# V_1.net
KiCad netlist of a schematic drawn in Altium Designer
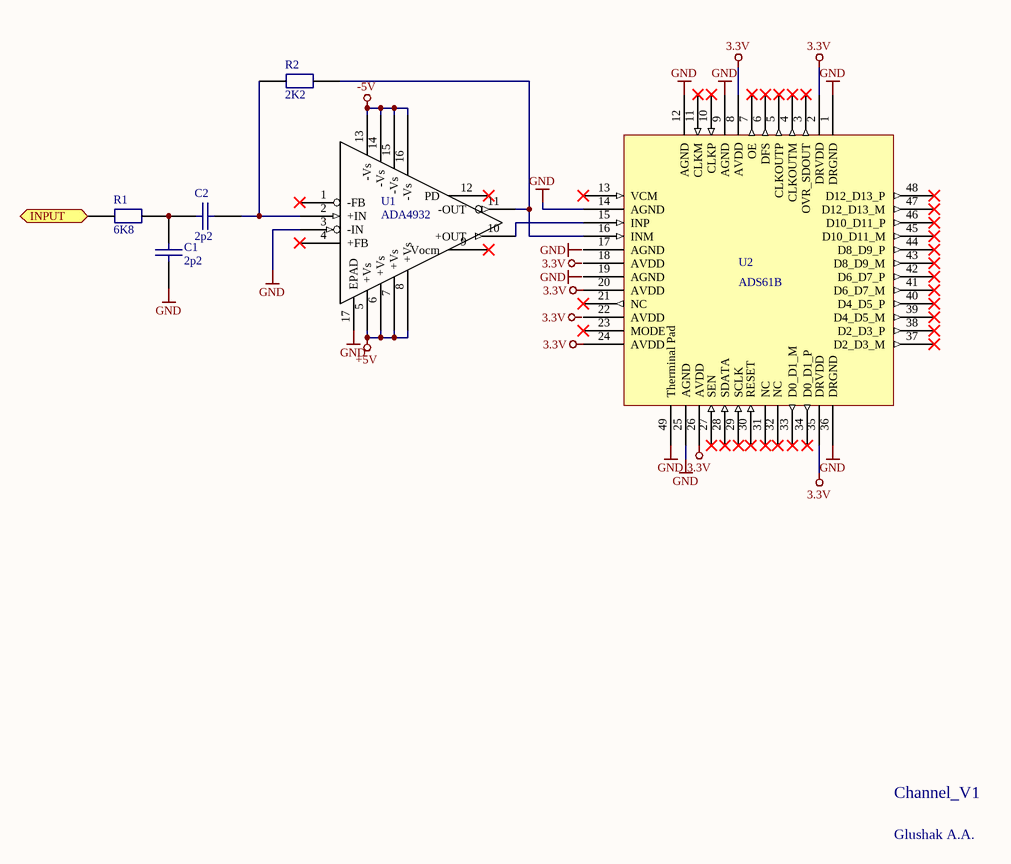
[diagram p0: V_1.SchDoc]

(export (version "E")
  (design (tool "Eeschema 10.0.6"))
  (components
    (comp (ref "C1") (value "2p2") (footprint "Cap0805") (libsource (lib "V_1") (part "Cap")))
    (comp (ref "C2") (value "2p2") (footprint "Cap0805") (libsource (lib "V_1") (part "Cap")))
    (comp (ref "R1") (value "6K8") (footprint "Res0805") (libsource (lib "V_1") (part "Res")))
    (comp (ref "R2") (value "2K2") (footprint "Res0805") (libsource (lib "V_1") (part "Res")))
    (comp (ref "U1") (value "ADA4932") (footprint "ADA4932") (libsource (lib "V_1") (part "ADA4932")))
    (comp (ref "U2") (value "ADS61B") (footprint "ADS61B49") (libsource (lib "V_1") (part "ADS61B49")))
  )
  (nets
    (net (code "1") (name "+5V") (class "Default")
      (node (ref "U1") (pin "5") (pinfunction "+Vs_5") (pintype "power_in"))
      (node (ref "U1") (pin "6") (pinfunction "+Vs_6") (pintype "power_in"))
      (node (ref "U1") (pin "7") (pinfunction "+Vs_7") (pintype "power_in"))
      (node (ref "U1") (pin "8") (pinfunction "+Vs_8") (pintype "power_in"))
    )
    (net (code "2") (name "-5V") (class "Default")
      (node (ref "U1") (pin "13") (pinfunction "-Vs_13") (pintype "power_in"))
      (node (ref "U1") (pin "14") (pinfunction "-Vs_14") (pintype "power_in"))
      (node (ref "U1") (pin "15") (pinfunction "-Vs_15") (pintype "power_in"))
      (node (ref "U1") (pin "16") (pinfunction "-Vs_16") (pintype "power_in"))
    )
    (net (code "3") (name "/INPUT") (class "Default")
      (node (ref "R1") (pin "1") (pinfunction "1_1") (pintype "passive"))
    )
    (net (code "4") (name "3.3V") (class "Default")
      (node (ref "U2") (pin "2") (pinfunction "DRVDD_2") (pintype "power_in"))
      (node (ref "U2") (pin "20") (pinfunction "AVDD_20") (pintype "power_in"))
      (node (ref "U2") (pin "24") (pinfunction "AVDD_24") (pintype "power_in"))
      (node (ref "U2") (pin "26") (pinfunction "AVDD_26") (pintype "power_in"))
      (node (ref "U2") (pin "35") (pinfunction "DRVDD_35") (pintype "power_in"))
      (node (ref "U2") (pin "8") (pinfunction "AVDD_8") (pintype "power_in"))
    )
    (net (code "5") (name "GND") (class "Default")
      (node (ref "C1") (pin "1") (pinfunction "1_1") (pintype "passive"))
      (node (ref "U1") (pin "17") (pinfunction "EPAD_17") (pintype "power_in"))
      (node (ref "U1") (pin "3") (pinfunction "-IN_3") (pintype "input"))
      (node (ref "U2") (pin "1") (pinfunction "DRGND_1") (pintype "power_in"))
      (node (ref "U2") (pin "12") (pinfunction "AGND_12") (pintype "power_in"))
      (node (ref "U2") (pin "14") (pinfunction "AGND_14") (pintype "power_in"))
      (node (ref "U2") (pin "25") (pinfunction "AGND_25") (pintype "power_in"))
      (node (ref "U2") (pin "36") (pinfunction "DRGND_36") (pintype "power_in"))
      (node (ref "U2") (pin "49") (pinfunction "Therminal_Pad_49") (pintype "power_in"))
      (node (ref "U2") (pin "9") (pinfunction "AGND_9") (pintype "power_in"))
    )
    (net (code "6") (name "Net-(C1-Pad2)") (class "Default")
      (node (ref "C1") (pin "2") (pinfunction "2_2") (pintype "passive"))
      (node (ref "C2") (pin "2") (pinfunction "2_2") (pintype "passive"))
      (node (ref "R1") (pin "2") (pinfunction "2_2") (pintype "passive"))
    )
    (net (code "7") (name "Net-(U1-+IN)") (class "Default")
      (node (ref "C2") (pin "1") (pinfunction "1_1") (pintype "passive"))
      (node (ref "R2") (pin "1") (pinfunction "1_1") (pintype "passive"))
      (node (ref "U1") (pin "2") (pinfunction "+IN_2") (pintype "input"))
    )
    (net (code "8") (name "Net-(U1-+OUT)") (class "Default")
      (node (ref "U1") (pin "10") (pinfunction "+OUT_10") (pintype "output"))
      (node (ref "U2") (pin "15") (pinfunction "INP_15") (pintype "input"))
    )
    (net (code "9") (name "Net-(U1--OUT)") (class "Default")
      (node (ref "R2") (pin "2") (pinfunction "2_2") (pintype "passive"))
      (node (ref "U1") (pin "11") (pinfunction "-OUT_11") (pintype "output"))
      (node (ref "U2") (pin "16") (pinfunction "INM_16") (pintype "input"))
    )
    (net (code "10") (name "unconnected-(U1-+FB-Pad4)") (class "Default")
      (node (ref "U1") (pin "4") (pinfunction "+FB_4") (pintype "passive+no_connect"))
    )
    (net (code "11") (name "unconnected-(U1--FB-Pad1)") (class "Default")
      (node (ref "U1") (pin "1") (pinfunction "-FB_1") (pintype "passive+no_connect"))
    )
    (net (code "12") (name "unconnected-(U1-PD-Pad12)") (class "Default")
      (node (ref "U1") (pin "12") (pinfunction "PD_12") (pintype "passive+no_connect"))
    )
    (net (code "13") (name "unconnected-(U1-Vocm-Pad9)") (class "Default")
      (node (ref "U1") (pin "9") (pinfunction "Vocm_9") (pintype "power_in+no_connect"))
    )
    (net (code "14") (name "unconnected-(U2-AGND-Pad17)") (class "Default")
      (node (ref "U2") (pin "17") (pinfunction "AGND_17") (pintype "power_in"))
    )
    (net (code "15") (name "unconnected-(U2-AGND-Pad19)") (class "Default")
      (node (ref "U2") (pin "19") (pinfunction "AGND_19") (pintype "power_in"))
    )
    (net (code "16") (name "unconnected-(U2-AVDD-Pad18)") (class "Default")
      (node (ref "U2") (pin "18") (pinfunction "AVDD_18") (pintype "power_in"))
    )
    (net (code "17") (name "unconnected-(U2-AVDD-Pad22)") (class "Default")
      (node (ref "U2") (pin "22") (pinfunction "AVDD_22") (pintype "power_in"))
    )
    (net (code "18") (name "unconnected-(U2-CLKM-Pad11)") (class "Default")
      (node (ref "U2") (pin "11") (pinfunction "CLKM_11") (pintype "input+no_connect"))
    )
    (net (code "19") (name "unconnected-(U2-CLKOUTM-Pad4)") (class "Default")
      (node (ref "U2") (pin "4") (pinfunction "CLKOUTM_4") (pintype "output+no_connect"))
    )
    (net (code "20") (name "unconnected-(U2-CLKOUTP-Pad5)") (class "Default")
      (node (ref "U2") (pin "5") (pinfunction "CLKOUTP_5") (pintype "output+no_connect"))
    )
    (net (code "21") (name "unconnected-(U2-CLKP-Pad10)") (class "Default")
      (node (ref "U2") (pin "10") (pinfunction "CLKP_10") (pintype "input+no_connect"))
    )
    (net (code "22") (name "unconnected-(U2-D0_D1_M-Pad33)") (class "Default")
      (node (ref "U2") (pin "33") (pinfunction "D0_D1_M_33") (pintype "output+no_connect"))
    )
    (net (code "23") (name "unconnected-(U2-D0_D1_P-Pad34)") (class "Default")
      (node (ref "U2") (pin "34") (pinfunction "D0_D1_P_34") (pintype "output+no_connect"))
    )
    (net (code "24") (name "unconnected-(U2-D2_D3_M-Pad37)") (class "Default")
      (node (ref "U2") (pin "37") (pinfunction "D2_D3_M_37") (pintype "output+no_connect"))
    )
    (net (code "25") (name "unconnected-(U2-D2_D3_P-Pad38)") (class "Default")
      (node (ref "U2") (pin "38") (pinfunction "D2_D3_P_38") (pintype "output+no_connect"))
    )
    (net (code "26") (name "unconnected-(U2-D4_D5_M-Pad39)") (class "Default")
      (node (ref "U2") (pin "39") (pinfunction "D4_D5_M_39") (pintype "output+no_connect"))
    )
    (net (code "27") (name "unconnected-(U2-D4_D5_P-Pad40)") (class "Default")
      (node (ref "U2") (pin "40") (pinfunction "D4_D5_P_40") (pintype "output+no_connect"))
    )
    (net (code "28") (name "unconnected-(U2-D6_D7_M-Pad41)") (class "Default")
      (node (ref "U2") (pin "41") (pinfunction "D6_D7_M_41") (pintype "output+no_connect"))
    )
    (net (code "29") (name "unconnected-(U2-D6_D7_P-Pad42)") (class "Default")
      (node (ref "U2") (pin "42") (pinfunction "D6_D7_P_42") (pintype "output+no_connect"))
    )
    (net (code "30") (name "unconnected-(U2-D8_D9_M-Pad43)") (class "Default")
      (node (ref "U2") (pin "43") (pinfunction "D8_D9_M_43") (pintype "output+no_connect"))
    )
    (net (code "31") (name "unconnected-(U2-D8_D9_P-Pad44)") (class "Default")
      (node (ref "U2") (pin "44") (pinfunction "D8_D9_P_44") (pintype "output+no_connect"))
    )
    (net (code "32") (name "unconnected-(U2-D10_D11_M-Pad45)") (class "Default")
      (node (ref "U2") (pin "45") (pinfunction "D10_D11_M_45") (pintype "output+no_connect"))
    )
    (net (code "33") (name "unconnected-(U2-D10_D11_P-Pad46)") (class "Default")
      (node (ref "U2") (pin "46") (pinfunction "D10_D11_P_46") (pintype "output+no_connect"))
    )
    (net (code "34") (name "unconnected-(U2-D12_D13_M-Pad47)") (class "Default")
      (node (ref "U2") (pin "47") (pinfunction "D12_D13_M_47") (pintype "output+no_connect"))
    )
    (net (code "35") (name "unconnected-(U2-D12_D13_P-Pad48)") (class "Default")
      (node (ref "U2") (pin "48") (pinfunction "D12_D13_P_48") (pintype "output+no_connect"))
    )
    (net (code "36") (name "unconnected-(U2-DFS-Pad6)") (class "Default")
      (node (ref "U2") (pin "6") (pinfunction "DFS_6") (pintype "output+no_connect"))
    )
    (net (code "37") (name "unconnected-(U2-MODE-Pad23)") (class "Default")
      (node (ref "U2") (pin "23") (pinfunction "MODE_23") (pintype "passive+no_connect"))
    )
    (net (code "38") (name "unconnected-(U2-NC-Pad21)") (class "Default")
      (node (ref "U2") (pin "21") (pinfunction "NC_21") (pintype "output+no_connect"))
    )
    (net (code "39") (name "unconnected-(U2-NC-Pad31)") (class "Default")
      (node (ref "U2") (pin "31") (pinfunction "NC_31") (pintype "passive+no_connect"))
    )
    (net (code "40") (name "unconnected-(U2-NC-Pad32)") (class "Default")
      (node (ref "U2") (pin "32") (pinfunction "NC_32") (pintype "passive+no_connect"))
    )
    (net (code "41") (name "unconnected-(U2-OE-Pad7)") (class "Default")
      (node (ref "U2") (pin "7") (pinfunction "OE_7") (pintype "output+no_connect"))
    )
    (net (code "42") (name "unconnected-(U2-OVR_SDOUT-Pad3)") (class "Default")
      (node (ref "U2") (pin "3") (pinfunction "OVR_SDOUT_3") (pintype "output+no_connect"))
    )
    (net (code "43") (name "unconnected-(U2-RESET-Pad30)") (class "Default")
      (node (ref "U2") (pin "30") (pinfunction "RESET_30") (pintype "input+no_connect"))
    )
    (net (code "44") (name "unconnected-(U2-SCLK-Pad29)") (class "Default")
      (node (ref "U2") (pin "29") (pinfunction "SCLK_29") (pintype "input+no_connect"))
    )
    (net (code "45") (name "unconnected-(U2-SDATA-Pad28)") (class "Default")
      (node (ref "U2") (pin "28") (pinfunction "SDATA_28") (pintype "input+no_connect"))
    )
    (net (code "46") (name "unconnected-(U2-SEN-Pad27)") (class "Default")
      (node (ref "U2") (pin "27") (pinfunction "SEN_27") (pintype "input+no_connect"))
    )
    (net (code "47") (name "unconnected-(U2-VCM-Pad13)") (class "Default")
      (node (ref "U2") (pin "13") (pinfunction "VCM_13") (pintype "input+no_connect"))
    )
  )
)
